# main.net
KiCad netlist of a schematic drawn in Altium Designer
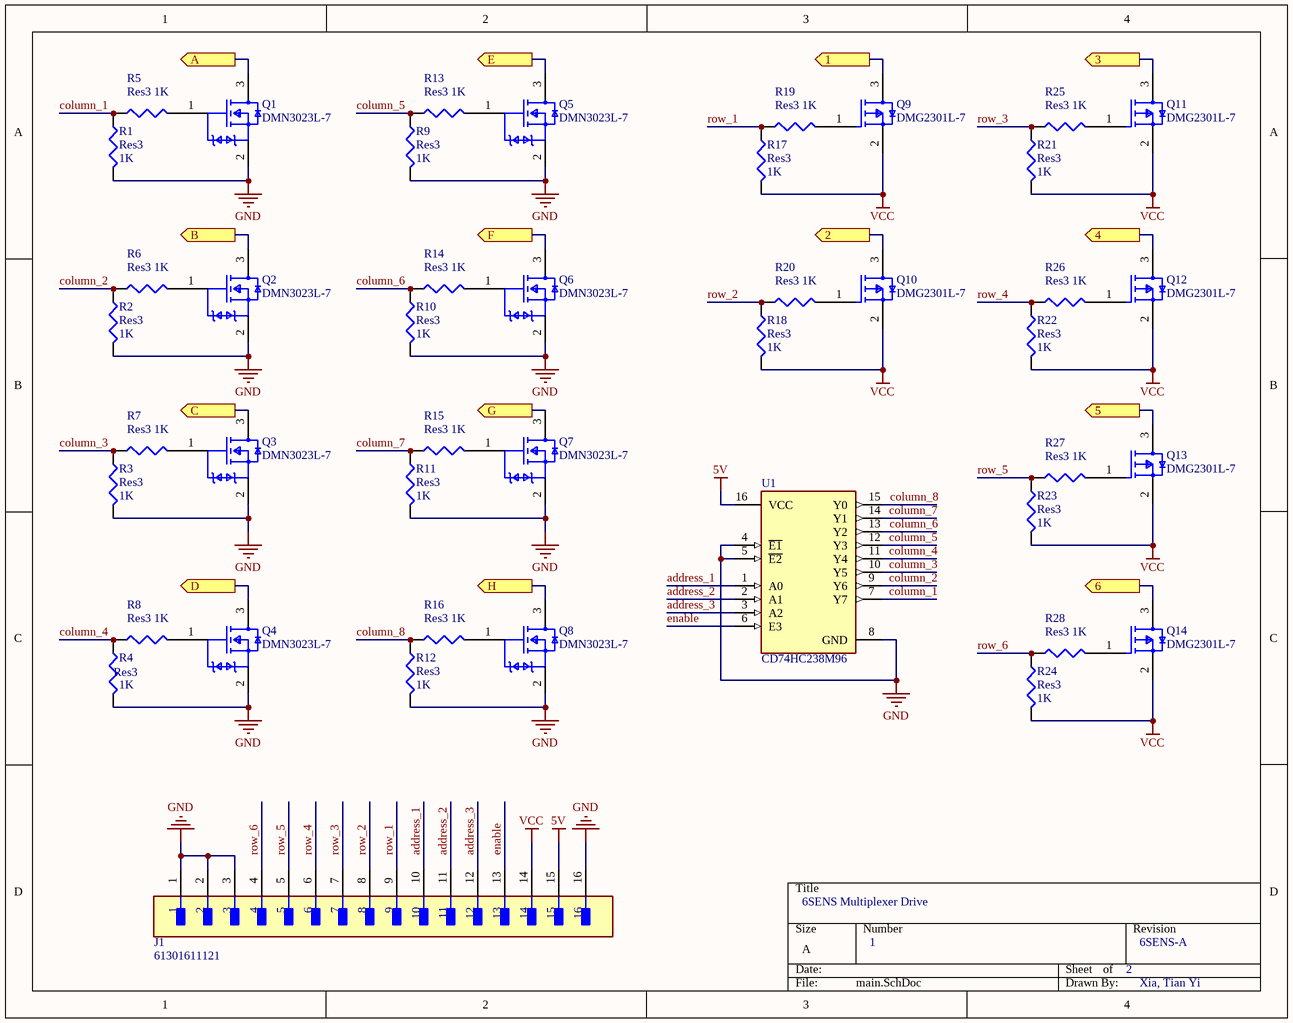
[diagram p0: main.SchDoc]

(export (version "E")
  (design (tool "Eeschema 10.0.6"))
  (components
    (comp (ref "J1")
      (value "61301611121")
      (footprint "FP-61301611121-MFG")
      (description "CONN HEADER VERT 16POS 2.54MM")
      (libsource (lib "Altium Content Vault") (part "e5c9d856941f54a8fdb498ab6b27a18"))
    )
    (comp (ref "Q1")
      (value "DMN3023L-7")
      (footprint "FP-SOT23-MFG")
      (description "MOSFET N-CH 30V 6.2A SOT23")
      (fields
        (field (name "OCTOPART") "https://octopart.com/dmn3023l-7-diodes+inc.-65294126")
        (field (name "MANUFACTURER") "Diodes Inc.")
      )
      (libsource (lib "Altium Content Vault") (part "8a460d0f3ed9f10fc88b37d9524c9e6"))
    )
    (comp (ref "Q2")
      (value "DMN3023L-7")
      (footprint "FP-SOT23-MFG")
      (description "MOSFET N-CH 30V 6.2A SOT23")
      (fields
        (field (name "OCTOPART") "https://octopart.com/dmn3023l-7-diodes+inc.-65294126")
        (field (name "MANUFACTURER") "Diodes Inc.")
      )
      (libsource (lib "Altium Content Vault") (part "8a460d0f3ed9f10fc88b37d9524c9e6"))
    )
    (comp (ref "Q3")
      (value "DMN3023L-7")
      (footprint "FP-SOT23-MFG")
      (description "MOSFET N-CH 30V 6.2A SOT23")
      (fields
        (field (name "OCTOPART") "https://octopart.com/dmn3023l-7-diodes+inc.-65294126")
        (field (name "MANUFACTURER") "Diodes Inc.")
      )
      (libsource (lib "Altium Content Vault") (part "8a460d0f3ed9f10fc88b37d9524c9e6"))
    )
    (comp (ref "Q4")
      (value "DMN3023L-7")
      (footprint "FP-SOT23-MFG")
      (description "MOSFET N-CH 30V 6.2A SOT23")
      (fields
        (field (name "OCTOPART") "https://octopart.com/dmn3023l-7-diodes+inc.-65294126")
        (field (name "MANUFACTURER") "Diodes Inc.")
      )
      (libsource (lib "Altium Content Vault") (part "8a460d0f3ed9f10fc88b37d9524c9e6"))
    )
    (comp (ref "Q5")
      (value "DMN3023L-7")
      (footprint "FP-SOT23-MFG")
      (description "MOSFET N-CH 30V 6.2A SOT23")
      (fields
        (field (name "OCTOPART") "https://octopart.com/dmn3023l-7-diodes+inc.-65294126")
        (field (name "MANUFACTURER") "Diodes Inc.")
      )
      (libsource (lib "Altium Content Vault") (part "8a460d0f3ed9f10fc88b37d9524c9e6"))
    )
    (comp (ref "Q6")
      (value "DMN3023L-7")
      (footprint "FP-SOT23-MFG")
      (description "MOSFET N-CH 30V 6.2A SOT23")
      (fields
        (field (name "OCTOPART") "https://octopart.com/dmn3023l-7-diodes+inc.-65294126")
        (field (name "MANUFACTURER") "Diodes Inc.")
      )
      (libsource (lib "Altium Content Vault") (part "8a460d0f3ed9f10fc88b37d9524c9e6"))
    )
    (comp (ref "Q7")
      (value "DMN3023L-7")
      (footprint "FP-SOT23-MFG")
      (description "MOSFET N-CH 30V 6.2A SOT23")
      (fields
        (field (name "OCTOPART") "https://octopart.com/dmn3023l-7-diodes+inc.-65294126")
        (field (name "MANUFACTURER") "Diodes Inc.")
      )
      (libsource (lib "Altium Content Vault") (part "8a460d0f3ed9f10fc88b37d9524c9e6"))
    )
    (comp (ref "Q8")
      (value "DMN3023L-7")
      (footprint "FP-SOT23-MFG")
      (description "MOSFET N-CH 30V 6.2A SOT23")
      (fields
        (field (name "OCTOPART") "https://octopart.com/dmn3023l-7-diodes+inc.-65294126")
        (field (name "MANUFACTURER") "Diodes Inc.")
      )
      (libsource (lib "Altium Content Vault") (part "8a460d0f3ed9f10fc88b37d9524c9e6"))
    )
    (comp (ref "Q9")
      (value "DMG2301L-7")
      (footprint "FP-SOT23-MFG")
      (description "MOSFET P-CH 20V 3A SOT23")
      (fields
        (field (name "MANUFACTURER") "Diodes Inc.")
        (field (name "OCTOPART") "https://octopart.com/dmg2301l-7-diodes+inc.-67250456")
      )
      (libsource (lib "Altium Content Vault") (part "b8f99f9e586195791e7fb11725ebaeb"))
    )
    (comp (ref "Q10")
      (value "DMG2301L-7")
      (footprint "FP-SOT23-MFG")
      (description "MOSFET P-CH 20V 3A SOT23")
      (fields
        (field (name "MANUFACTURER") "Diodes Inc.")
        (field (name "OCTOPART") "https://octopart.com/dmg2301l-7-diodes+inc.-67250456")
      )
      (libsource (lib "Altium Content Vault") (part "b8f99f9e586195791e7fb11725ebaeb"))
    )
    (comp (ref "Q11")
      (value "DMG2301L-7")
      (footprint "FP-SOT23-MFG")
      (description "MOSFET P-CH 20V 3A SOT23")
      (fields
        (field (name "MANUFACTURER") "Diodes Inc.")
        (field (name "OCTOPART") "https://octopart.com/dmg2301l-7-diodes+inc.-67250456")
      )
      (libsource (lib "Altium Content Vault") (part "b8f99f9e586195791e7fb11725ebaeb"))
    )
    (comp (ref "Q12")
      (value "DMG2301L-7")
      (footprint "FP-SOT23-MFG")
      (description "MOSFET P-CH 20V 3A SOT23")
      (fields
        (field (name "MANUFACTURER") "Diodes Inc.")
        (field (name "OCTOPART") "https://octopart.com/dmg2301l-7-diodes+inc.-67250456")
      )
      (libsource (lib "Altium Content Vault") (part "b8f99f9e586195791e7fb11725ebaeb"))
    )
    (comp (ref "Q13")
      (value "DMG2301L-7")
      (footprint "FP-SOT23-MFG")
      (description "MOSFET P-CH 20V 3A SOT23")
      (fields
        (field (name "MANUFACTURER") "Diodes Inc.")
        (field (name "OCTOPART") "https://octopart.com/dmg2301l-7-diodes+inc.-67250456")
      )
      (libsource (lib "Altium Content Vault") (part "b8f99f9e586195791e7fb11725ebaeb"))
    )
    (comp (ref "Q14")
      (value "DMG2301L-7")
      (footprint "FP-SOT23-MFG")
      (description "MOSFET P-CH 20V 3A SOT23")
      (fields
        (field (name "MANUFACTURER") "Diodes Inc.")
        (field (name "OCTOPART") "https://octopart.com/dmg2301l-7-diodes+inc.-67250456")
      )
      (libsource (lib "Altium Content Vault") (part "b8f99f9e586195791e7fb11725ebaeb"))
    )
    (comp (ref "R1")
      (value "Res3")
      (footprint "J1-0603")
      (description "Resistor")
      (fields (field (name "ALTIUM_VALUE") "1K") (field (name "PUBLISHER") "Altium Limited"))
      (libsource (lib "Miscellaneous Devices") (part "Res3"))
    )
    (comp (ref "R2")
      (value "Res3")
      (footprint "J1-0603")
      (description "Resistor")
      (fields (field (name "ALTIUM_VALUE") "1K") (field (name "PUBLISHER") "Altium Limited"))
      (libsource (lib "Miscellaneous Devices") (part "Res3"))
    )
    (comp (ref "R3")
      (value "Res3")
      (footprint "J1-0603")
      (description "Resistor")
      (fields (field (name "ALTIUM_VALUE") "1K") (field (name "PUBLISHER") "Altium Limited"))
      (libsource (lib "Miscellaneous Devices") (part "Res3"))
    )
    (comp (ref "R4")
      (value "Res3")
      (footprint "J1-0603")
      (description "Resistor")
      (fields (field (name "ALTIUM_VALUE") "1K") (field (name "PUBLISHER") "Altium Limited"))
      (libsource (lib "Miscellaneous Devices") (part "Res3"))
    )
    (comp (ref "R5")
      (value "Res3")
      (footprint "J1-0603")
      (description "Resistor")
      (fields (field (name "ALTIUM_VALUE") "1K") (field (name "PUBLISHER") "Altium Limited"))
      (libsource (lib "Miscellaneous Devices") (part "Res3"))
    )
    (comp (ref "R6")
      (value "Res3")
      (footprint "J1-0603")
      (description "Resistor")
      (fields (field (name "ALTIUM_VALUE") "1K") (field (name "PUBLISHER") "Altium Limited"))
      (libsource (lib "Miscellaneous Devices") (part "Res3"))
    )
    (comp (ref "R7")
      (value "Res3")
      (footprint "J1-0603")
      (description "Resistor")
      (fields (field (name "ALTIUM_VALUE") "1K") (field (name "PUBLISHER") "Altium Limited"))
      (libsource (lib "Miscellaneous Devices") (part "Res3"))
    )
    (comp (ref "R8")
      (value "Res3")
      (footprint "J1-0603")
      (description "Resistor")
      (fields (field (name "ALTIUM_VALUE") "1K") (field (name "PUBLISHER") "Altium Limited"))
      (libsource (lib "Miscellaneous Devices") (part "Res3"))
    )
    (comp (ref "R9")
      (value "Res3")
      (footprint "J1-0603")
      (description "Resistor")
      (fields (field (name "ALTIUM_VALUE") "1K") (field (name "PUBLISHER") "Altium Limited"))
      (libsource (lib "Miscellaneous Devices") (part "Res3"))
    )
    (comp (ref "R10")
      (value "Res3")
      (footprint "J1-0603")
      (description "Resistor")
      (fields (field (name "ALTIUM_VALUE") "1K") (field (name "PUBLISHER") "Altium Limited"))
      (libsource (lib "Miscellaneous Devices") (part "Res3"))
    )
    (comp (ref "R11")
      (value "Res3")
      (footprint "J1-0603")
      (description "Resistor")
      (fields (field (name "ALTIUM_VALUE") "1K") (field (name "PUBLISHER") "Altium Limited"))
      (libsource (lib "Miscellaneous Devices") (part "Res3"))
    )
    (comp (ref "R12")
      (value "Res3")
      (footprint "J1-0603")
      (description "Resistor")
      (fields (field (name "ALTIUM_VALUE") "1K") (field (name "PUBLISHER") "Altium Limited"))
      (libsource (lib "Miscellaneous Devices") (part "Res3"))
    )
    (comp (ref "R13")
      (value "Res3")
      (footprint "J1-0603")
      (description "Resistor")
      (fields (field (name "ALTIUM_VALUE") "1K") (field (name "PUBLISHER") "Altium Limited"))
      (libsource (lib "Miscellaneous Devices") (part "Res3"))
    )
    (comp (ref "R14")
      (value "Res3")
      (footprint "J1-0603")
      (description "Resistor")
      (fields (field (name "ALTIUM_VALUE") "1K") (field (name "PUBLISHER") "Altium Limited"))
      (libsource (lib "Miscellaneous Devices") (part "Res3"))
    )
    (comp (ref "R15")
      (value "Res3")
      (footprint "J1-0603")
      (description "Resistor")
      (fields (field (name "ALTIUM_VALUE") "1K") (field (name "PUBLISHER") "Altium Limited"))
      (libsource (lib "Miscellaneous Devices") (part "Res3"))
    )
    (comp (ref "R16")
      (value "Res3")
      (footprint "J1-0603")
      (description "Resistor")
      (fields (field (name "ALTIUM_VALUE") "1K") (field (name "PUBLISHER") "Altium Limited"))
      (libsource (lib "Miscellaneous Devices") (part "Res3"))
    )
    (comp (ref "R17")
      (value "Res3")
      (footprint "J1-0603")
      (description "Resistor")
      (fields (field (name "ALTIUM_VALUE") "1K") (field (name "PUBLISHER") "Altium Limited"))
      (libsource (lib "Miscellaneous Devices") (part "Res3"))
    )
    (comp (ref "R18")
      (value "Res3")
      (footprint "J1-0603")
      (description "Resistor")
      (fields (field (name "ALTIUM_VALUE") "1K") (field (name "PUBLISHER") "Altium Limited"))
      (libsource (lib "Miscellaneous Devices") (part "Res3"))
    )
    (comp (ref "R19")
      (value "Res3")
      (footprint "J1-0603")
      (description "Resistor")
      (fields (field (name "ALTIUM_VALUE") "1K") (field (name "PUBLISHER") "Altium Limited"))
      (libsource (lib "Miscellaneous Devices") (part "Res3"))
    )
    (comp (ref "R20")
      (value "Res3")
      (footprint "J1-0603")
      (description "Resistor")
      (fields (field (name "ALTIUM_VALUE") "1K") (field (name "PUBLISHER") "Altium Limited"))
      (libsource (lib "Miscellaneous Devices") (part "Res3"))
    )
    (comp (ref "R21")
      (value "Res3")
      (footprint "J1-0603")
      (description "Resistor")
      (fields (field (name "ALTIUM_VALUE") "1K") (field (name "PUBLISHER") "Altium Limited"))
      (libsource (lib "Miscellaneous Devices") (part "Res3"))
    )
    (comp (ref "R22")
      (value "Res3")
      (footprint "J1-0603")
      (description "Resistor")
      (fields (field (name "ALTIUM_VALUE") "1K") (field (name "PUBLISHER") "Altium Limited"))
      (libsource (lib "Miscellaneous Devices") (part "Res3"))
    )
    (comp (ref "R23")
      (value "Res3")
      (footprint "J1-0603")
      (description "Resistor")
      (fields (field (name "ALTIUM_VALUE") "1K") (field (name "PUBLISHER") "Altium Limited"))
      (libsource (lib "Miscellaneous Devices") (part "Res3"))
    )
    (comp (ref "R24")
      (value "Res3")
      (footprint "J1-0603")
      (description "Resistor")
      (fields (field (name "ALTIUM_VALUE") "1K") (field (name "PUBLISHER") "Altium Limited"))
      (libsource (lib "Miscellaneous Devices") (part "Res3"))
    )
    (comp (ref "R25")
      (value "Res3")
      (footprint "J1-0603")
      (description "Resistor")
      (fields (field (name "ALTIUM_VALUE") "1K") (field (name "PUBLISHER") "Altium Limited"))
      (libsource (lib "Miscellaneous Devices") (part "Res3"))
    )
    (comp (ref "R26")
      (value "Res3")
      (footprint "J1-0603")
      (description "Resistor")
      (fields (field (name "ALTIUM_VALUE") "1K") (field (name "PUBLISHER") "Altium Limited"))
      (libsource (lib "Miscellaneous Devices") (part "Res3"))
    )
    (comp (ref "R27")
      (value "Res3")
      (footprint "J1-0603")
      (description "Resistor")
      (fields (field (name "ALTIUM_VALUE") "1K") (field (name "PUBLISHER") "Altium Limited"))
      (libsource (lib "Miscellaneous Devices") (part "Res3"))
    )
    (comp (ref "R28")
      (value "Res3")
      (footprint "J1-0603")
      (description "Resistor")
      (fields (field (name "ALTIUM_VALUE") "1K") (field (name "PUBLISHER") "Altium Limited"))
      (libsource (lib "Miscellaneous Devices") (part "Res3"))
    )
    (comp (ref "U1")
      (value "CD74HC238M96")
      (footprint "FP-D0016A-MFG")
      (description "IC 3-8 DECODER/DEMUX HS 16-SOIC")
      (fields
        (field (name "OCTOPART") "https://octopart.com/cd74hc238m96-texas+instruments-1365099")
        (field (name "MANUFACTURER") "Texas Instruments")
      )
      (libsource (lib "Altium Content Vault") (part "7b0648f9a0c2955108857481398d18b"))
    )
  )
  (nets
    (net (code "1") (name "/1") (class "Default")
      (node (ref "Q9") (pin "3") (pinfunction "D_3") (pintype "passive"))
    )
    (net (code "2") (name "/2") (class "Default")
      (node (ref "Q10") (pin "3") (pinfunction "D_3") (pintype "passive"))
    )
    (net (code "3") (name "/3") (class "Default")
      (node (ref "Q11") (pin "3") (pinfunction "D_3") (pintype "passive"))
    )
    (net (code "4") (name "/4") (class "Default")
      (node (ref "Q12") (pin "3") (pinfunction "D_3") (pintype "passive"))
    )
    (net (code "5") (name "/5") (class "Default")
      (node (ref "Q13") (pin "3") (pinfunction "D_3") (pintype "passive"))
    )
    (net (code "6") (name "/6") (class "Default")
      (node (ref "Q14") (pin "3") (pinfunction "D_3") (pintype "passive"))
    )
    (net (code "7") (name "/A") (class "Default")
      (node (ref "Q1") (pin "3") (pinfunction "D_3") (pintype "passive"))
    )
    (net (code "8") (name "/B") (class "Default")
      (node (ref "Q2") (pin "3") (pinfunction "D_3") (pintype "passive"))
    )
    (net (code "9") (name "/C") (class "Default")
      (node (ref "Q3") (pin "3") (pinfunction "D_3") (pintype "passive"))
    )
    (net (code "10") (name "/D") (class "Default")
      (node (ref "Q4") (pin "3") (pinfunction "D_3") (pintype "passive"))
    )
    (net (code "11") (name "/E") (class "Default")
      (node (ref "Q5") (pin "3") (pinfunction "D_3") (pintype "passive"))
    )
    (net (code "12") (name "/F") (class "Default")
      (node (ref "Q6") (pin "3") (pinfunction "D_3") (pintype "passive"))
    )
    (net (code "13") (name "/G") (class "Default")
      (node (ref "Q7") (pin "3") (pinfunction "D_3") (pintype "passive"))
    )
    (net (code "14") (name "/H") (class "Default")
      (node (ref "Q8") (pin "3") (pinfunction "D_3") (pintype "passive"))
    )
    (net (code "15") (name "/address_1") (class "Default")
      (node (ref "J1") (pin "10") (pinfunction "10_10") (pintype "passive"))
      (node (ref "U1") (pin "1") (pinfunction "A0_1") (pintype "input"))
    )
    (net (code "16") (name "/address_2") (class "Default")
      (node (ref "J1") (pin "11") (pinfunction "11_11") (pintype "passive"))
      (node (ref "U1") (pin "2") (pinfunction "A1_2") (pintype "input"))
    )
    (net (code "17") (name "/address_3") (class "Default")
      (node (ref "J1") (pin "12") (pinfunction "12_12") (pintype "passive"))
      (node (ref "U1") (pin "3") (pinfunction "A2_3") (pintype "input"))
    )
    (net (code "18") (name "/column_1") (class "Default")
      (node (ref "R1") (pin "1") (pinfunction "1_1") (pintype "passive"))
      (node (ref "R5") (pin "1") (pinfunction "1_1") (pintype "passive"))
      (node (ref "U1") (pin "7") (pinfunction "Y7_7") (pintype "output"))
    )
    (net (code "19") (name "/column_2") (class "Default")
      (node (ref "R2") (pin "1") (pinfunction "1_1") (pintype "passive"))
      (node (ref "R6") (pin "1") (pinfunction "1_1") (pintype "passive"))
      (node (ref "U1") (pin "9") (pinfunction "Y6_9") (pintype "output"))
    )
    (net (code "20") (name "/column_3") (class "Default")
      (node (ref "R3") (pin "1") (pinfunction "1_1") (pintype "passive"))
      (node (ref "R7") (pin "1") (pinfunction "1_1") (pintype "passive"))
      (node (ref "U1") (pin "10") (pinfunction "Y5_10") (pintype "output"))
    )
    (net (code "21") (name "/column_4") (class "Default")
      (node (ref "R4") (pin "1") (pinfunction "1_1") (pintype "passive"))
      (node (ref "R8") (pin "1") (pinfunction "1_1") (pintype "passive"))
      (node (ref "U1") (pin "11") (pinfunction "Y4_11") (pintype "output"))
    )
    (net (code "22") (name "/column_5") (class "Default")
      (node (ref "R13") (pin "1") (pinfunction "1_1") (pintype "passive"))
      (node (ref "R9") (pin "1") (pinfunction "1_1") (pintype "passive"))
      (node (ref "U1") (pin "12") (pinfunction "Y3_12") (pintype "output"))
    )
    (net (code "23") (name "/column_6") (class "Default")
      (node (ref "R10") (pin "1") (pinfunction "1_1") (pintype "passive"))
      (node (ref "R14") (pin "1") (pinfunction "1_1") (pintype "passive"))
      (node (ref "U1") (pin "13") (pinfunction "Y2_13") (pintype "output"))
    )
    (net (code "24") (name "/column_7") (class "Default")
      (node (ref "R11") (pin "1") (pinfunction "1_1") (pintype "passive"))
      (node (ref "R15") (pin "1") (pinfunction "1_1") (pintype "passive"))
      (node (ref "U1") (pin "14") (pinfunction "Y1_14") (pintype "output"))
    )
    (net (code "25") (name "/column_8") (class "Default")
      (node (ref "R12") (pin "1") (pinfunction "1_1") (pintype "passive"))
      (node (ref "R16") (pin "1") (pinfunction "1_1") (pintype "passive"))
      (node (ref "U1") (pin "15") (pinfunction "Y0_15") (pintype "output"))
    )
    (net (code "26") (name "/enable") (class "Default")
      (node (ref "J1") (pin "13") (pinfunction "13_13") (pintype "passive"))
      (node (ref "U1") (pin "6") (pinfunction "E3_6") (pintype "input"))
    )
    (net (code "27") (name "/row_1") (class "Default")
      (node (ref "J1") (pin "9") (pinfunction "9_9") (pintype "passive"))
      (node (ref "R17") (pin "1") (pinfunction "1_1") (pintype "passive"))
      (node (ref "R19") (pin "1") (pinfunction "1_1") (pintype "passive"))
    )
    (net (code "28") (name "/row_2") (class "Default")
      (node (ref "J1") (pin "8") (pinfunction "8_8") (pintype "passive"))
      (node (ref "R18") (pin "1") (pinfunction "1_1") (pintype "passive"))
      (node (ref "R20") (pin "1") (pinfunction "1_1") (pintype "passive"))
    )
    (net (code "29") (name "/row_3") (class "Default")
      (node (ref "J1") (pin "7") (pinfunction "7_7") (pintype "passive"))
      (node (ref "R21") (pin "1") (pinfunction "1_1") (pintype "passive"))
      (node (ref "R25") (pin "1") (pinfunction "1_1") (pintype "passive"))
    )
    (net (code "30") (name "/row_4") (class "Default")
      (node (ref "J1") (pin "6") (pinfunction "6_6") (pintype "passive"))
      (node (ref "R22") (pin "1") (pinfunction "1_1") (pintype "passive"))
      (node (ref "R26") (pin "1") (pinfunction "1_1") (pintype "passive"))
    )
    (net (code "31") (name "/row_5") (class "Default")
      (node (ref "J1") (pin "5") (pinfunction "5_5") (pintype "passive"))
      (node (ref "R23") (pin "1") (pinfunction "1_1") (pintype "passive"))
      (node (ref "R27") (pin "1") (pinfunction "1_1") (pintype "passive"))
    )
    (net (code "32") (name "/row_6") (class "Default")
      (node (ref "J1") (pin "4") (pinfunction "4_4") (pintype "passive"))
      (node (ref "R24") (pin "1") (pinfunction "1_1") (pintype "passive"))
      (node (ref "R28") (pin "1") (pinfunction "1_1") (pintype "passive"))
    )
    (net (code "33") (name "5V") (class "Default")
      (node (ref "J1") (pin "15") (pinfunction "15_15") (pintype "passive"))
      (node (ref "U1") (pin "16") (pinfunction "VCC_16") (pintype "power_in"))
    )
    (net (code "34") (name "GND") (class "Default")
      (node (ref "J1") (pin "1") (pinfunction "1_1") (pintype "passive"))
      (node (ref "J1") (pin "16") (pinfunction "16_16") (pintype "passive"))
      (node (ref "J1") (pin "2") (pinfunction "2_2") (pintype "passive"))
      (node (ref "J1") (pin "3") (pinfunction "3_3") (pintype "passive"))
      (node (ref "Q1") (pin "2") (pinfunction "S_2") (pintype "passive"))
      (node (ref "Q2") (pin "2") (pinfunction "S_2") (pintype "passive"))
      (node (ref "Q3") (pin "2") (pinfunction "S_2") (pintype "passive"))
      (node (ref "Q4") (pin "2") (pinfunction "S_2") (pintype "passive"))
      (node (ref "Q5") (pin "2") (pinfunction "S_2") (pintype "passive"))
      (node (ref "Q6") (pin "2") (pinfunction "S_2") (pintype "passive"))
      (node (ref "Q7") (pin "2") (pinfunction "S_2") (pintype "passive"))
      (node (ref "Q8") (pin "2") (pinfunction "S_2") (pintype "passive"))
      (node (ref "R1") (pin "2") (pinfunction "2_2") (pintype "passive"))
      (node (ref "R10") (pin "2") (pinfunction "2_2") (pintype "passive"))
      (node (ref "R11") (pin "2") (pinfunction "2_2") (pintype "passive"))
      (node (ref "R12") (pin "2") (pinfunction "2_2") (pintype "passive"))
      (node (ref "R2") (pin "2") (pinfunction "2_2") (pintype "passive"))
      (node (ref "R3") (pin "2") (pinfunction "2_2") (pintype "passive"))
      (node (ref "R4") (pin "2") (pinfunction "2_2") (pintype "passive"))
      (node (ref "R9") (pin "2") (pinfunction "2_2") (pintype "passive"))
      (node (ref "U1") (pin "4") (pinfunction "~{E1}_4") (pintype "input"))
      (node (ref "U1") (pin "5") (pinfunction "~{E2}_5") (pintype "input"))
      (node (ref "U1") (pin "8") (pinfunction "GND_8") (pintype "power_in"))
    )
    (net (code "35") (name "Net-(Q1-G)") (class "Default")
      (node (ref "Q1") (pin "1") (pinfunction "G_1") (pintype "passive"))
      (node (ref "R5") (pin "2") (pinfunction "2_2") (pintype "passive"))
    )
    (net (code "36") (name "Net-(Q2-G)") (class "Default")
      (node (ref "Q2") (pin "1") (pinfunction "G_1") (pintype "passive"))
      (node (ref "R6") (pin "2") (pinfunction "2_2") (pintype "passive"))
    )
    (net (code "37") (name "Net-(Q3-G)") (class "Default")
      (node (ref "Q3") (pin "1") (pinfunction "G_1") (pintype "passive"))
      (node (ref "R7") (pin "2") (pinfunction "2_2") (pintype "passive"))
    )
    (net (code "38") (name "Net-(Q4-G)") (class "Default")
      (node (ref "Q4") (pin "1") (pinfunction "G_1") (pintype "passive"))
      (node (ref "R8") (pin "2") (pinfunction "2_2") (pintype "passive"))
    )
    (net (code "39") (name "Net-(Q5-G)") (class "Default")
      (node (ref "Q5") (pin "1") (pinfunction "G_1") (pintype "passive"))
      (node (ref "R13") (pin "2") (pinfunction "2_2") (pintype "passive"))
    )
    (net (code "40") (name "Net-(Q6-G)") (class "Default")
      (node (ref "Q6") (pin "1") (pinfunction "G_1") (pintype "passive"))
      (node (ref "R14") (pin "2") (pinfunction "2_2") (pintype "passive"))
    )
    (net (code "41") (name "Net-(Q7-G)") (class "Default")
      (node (ref "Q7") (pin "1") (pinfunction "G_1") (pintype "passive"))
      (node (ref "R15") (pin "2") (pinfunction "2_2") (pintype "passive"))
    )
    (net (code "42") (name "Net-(Q8-G)") (class "Default")
      (node (ref "Q8") (pin "1") (pinfunction "G_1") (pintype "passive"))
      (node (ref "R16") (pin "2") (pinfunction "2_2") (pintype "passive"))
    )
    (net (code "43") (name "Net-(Q9-G)") (class "Default")
      (node (ref "Q9") (pin "1") (pinfunction "G_1") (pintype "passive"))
      (node (ref "R19") (pin "2") (pinfunction "2_2") (pintype "passive"))
    )
    (net (code "44") (name "Net-(Q10-G)") (class "Default")
      (node (ref "Q10") (pin "1") (pinfunction "G_1") (pintype "passive"))
      (node (ref "R20") (pin "2") (pinfunction "2_2") (pintype "passive"))
    )
    (net (code "45") (name "Net-(Q11-G)") (class "Default")
      (node (ref "Q11") (pin "1") (pinfunction "G_1") (pintype "passive"))
      (node (ref "R25") (pin "2") (pinfunction "2_2") (pintype "passive"))
    )
    (net (code "46") (name "Net-(Q12-G)") (class "Default")
      (node (ref "Q12") (pin "1") (pinfunction "G_1") (pintype "passive"))
      (node (ref "R26") (pin "2") (pinfunction "2_2") (pintype "passive"))
    )
    (net (code "47") (name "Net-(Q13-G)") (class "Default")
      (node (ref "Q13") (pin "1") (pinfunction "G_1") (pintype "passive"))
      (node (ref "R27") (pin "2") (pinfunction "2_2") (pintype "passive"))
    )
    (net (code "48") (name "Net-(Q14-G)") (class "Default")
      (node (ref "Q14") (pin "1") (pinfunction "G_1") (pintype "passive"))
      (node (ref "R28") (pin "2") (pinfunction "2_2") (pintype "passive"))
    )
    (net (code "49") (name "VCC") (class "Default")
      (node (ref "J1") (pin "14") (pinfunction "14_14") (pintype "passive"))
      (node (ref "Q10") (pin "2") (pinfunction "S_2") (pintype "passive"))
      (node (ref "Q11") (pin "2") (pinfunction "S_2") (pintype "passive"))
      (node (ref "Q12") (pin "2") (pinfunction "S_2") (pintype "passive"))
      (node (ref "Q13") (pin "2") (pinfunction "S_2") (pintype "passive"))
      (node (ref "Q14") (pin "2") (pinfunction "S_2") (pintype "passive"))
      (node (ref "Q9") (pin "2") (pinfunction "S_2") (pintype "passive"))
      (node (ref "R17") (pin "2") (pinfunction "2_2") (pintype "passive"))
      (node (ref "R18") (pin "2") (pinfunction "2_2") (pintype "passive"))
      (node (ref "R21") (pin "2") (pinfunction "2_2") (pintype "passive"))
      (node (ref "R22") (pin "2") (pinfunction "2_2") (pintype "passive"))
      (node (ref "R23") (pin "2") (pinfunction "2_2") (pintype "passive"))
      (node (ref "R24") (pin "2") (pinfunction "2_2") (pintype "passive"))
    )
  )
)
